# ESP32_S3_MINI.net
KiCad netlist of a schematic drawn in Altium Designer
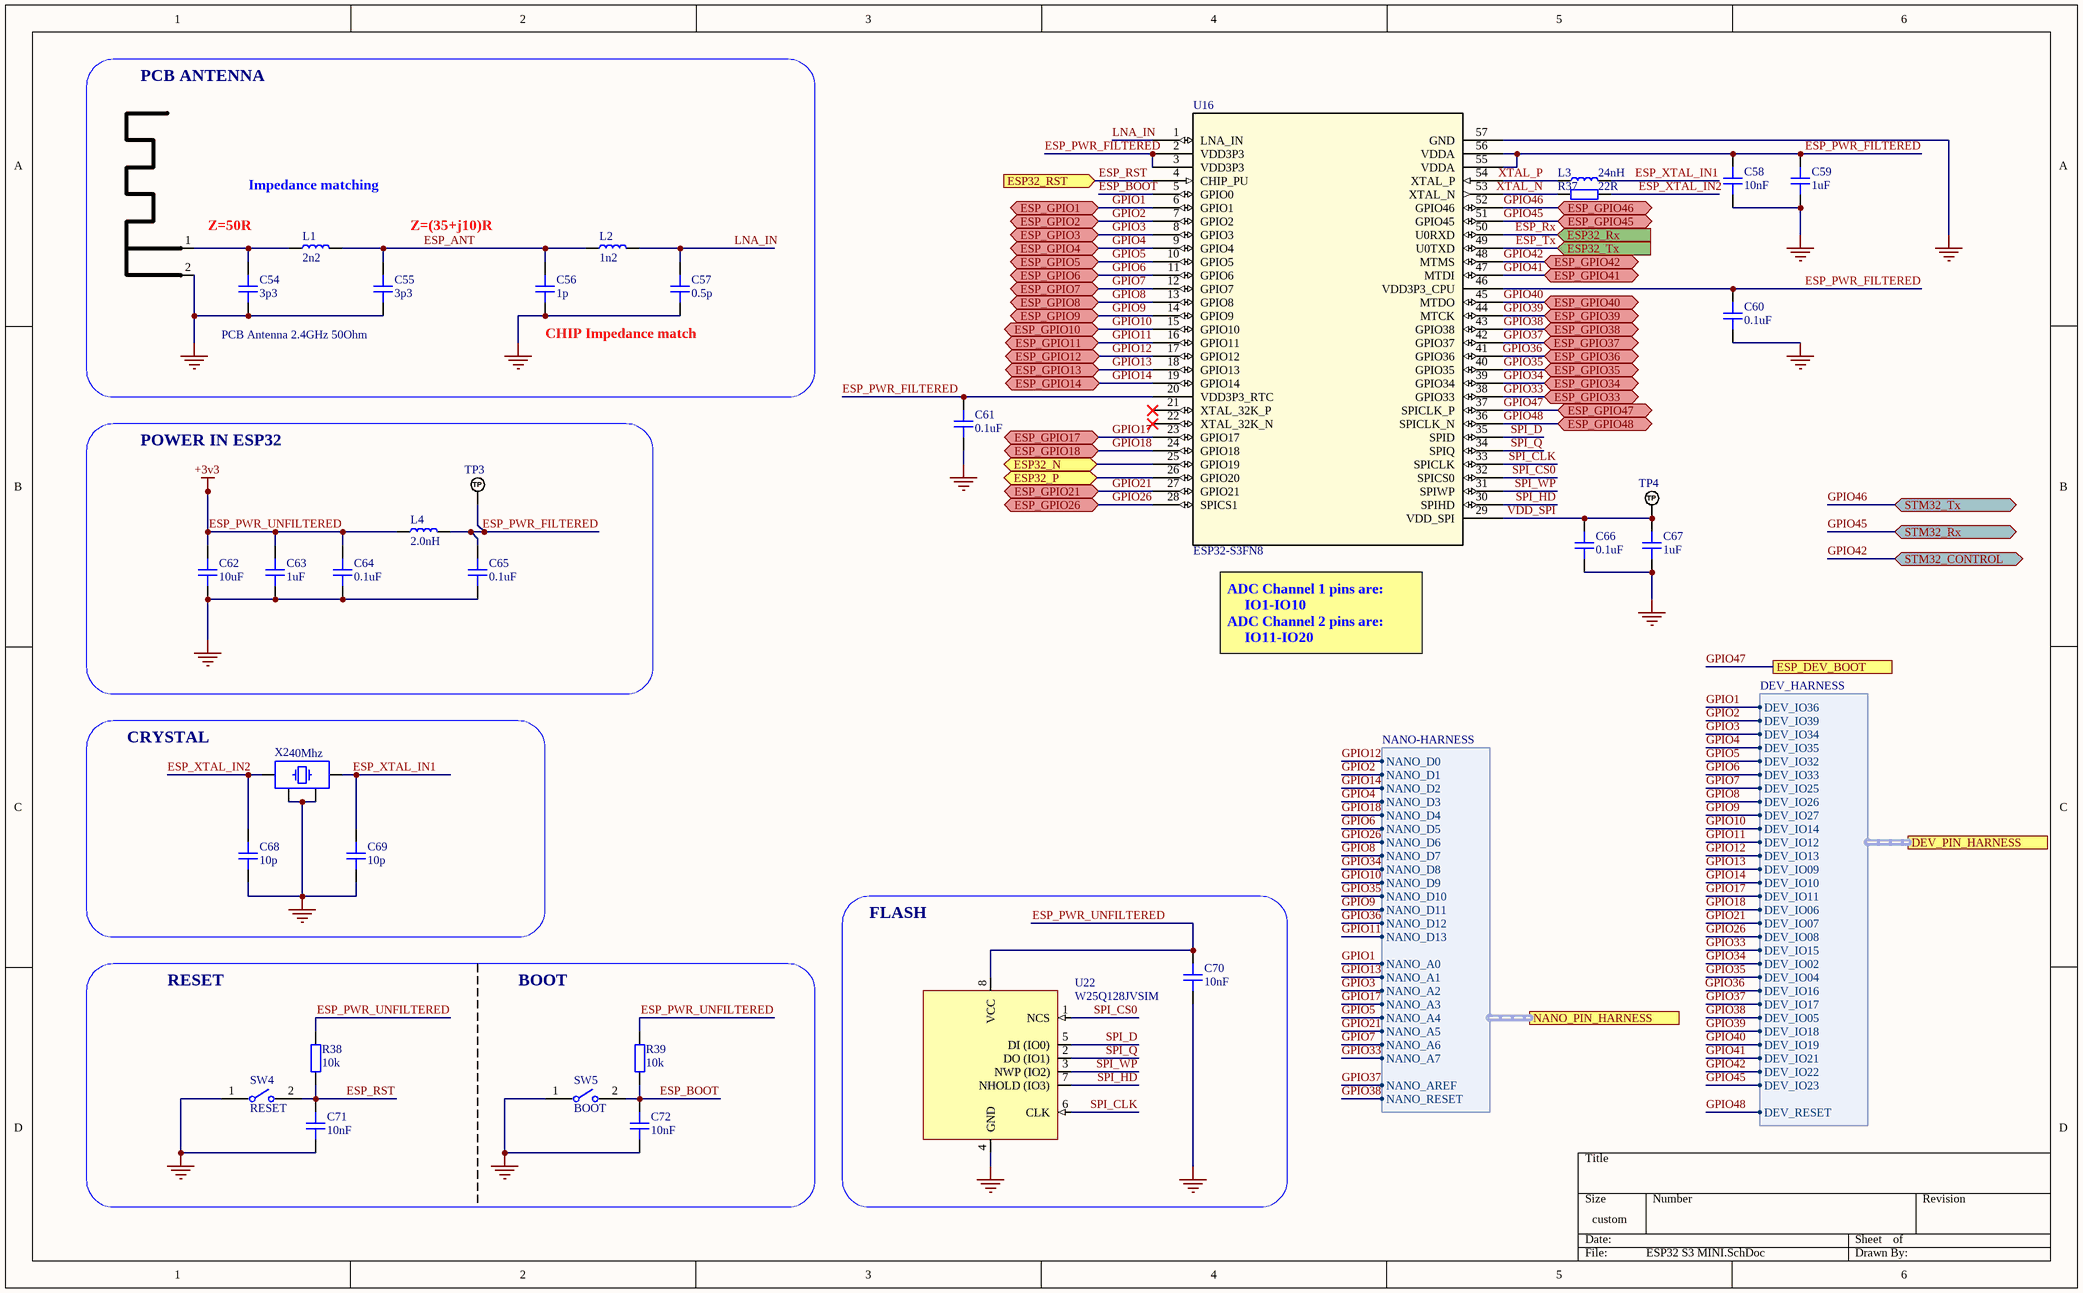
[diagram p0: ESP32 S3 MINI.SchDoc]

(export (version "E")
  (design (tool "Eeschema 10.0.6"))
  (components
    (comp (ref "ANT1")
      (value "PCB Antenna 2.4GHz 50Ohm")
      (footprint "ANT_IFA_USB_2_4GHZ_50R")
      (description "Inverted F 2.4GHz ISM PCB Antenna 50 Ohm")
      (libsource (lib "Schematic-Lib-PhilsLab") (part "ANT_IFA_USB_2_4GHZ_50R"))
    )
    (comp (ref "C54")
      (value "3p3")
      (footprint "CAP_0603")
      (description "Capacitor SMD 0603")
      (libsource (lib "Schematic-Lib-PhilsLab") (part "CAP_0603"))
    )
    (comp (ref "C55")
      (value "3p3")
      (footprint "CAP_0603")
      (description "Capacitor SMD 0603")
      (libsource (lib "Schematic-Lib-PhilsLab") (part "CAP_0603"))
    )
    (comp (ref "C56")
      (value "1p")
      (footprint "CAP_0603")
      (description "Capacitor SMD 0603")
      (libsource (lib "Schematic-Lib-PhilsLab") (part "CAP_0603"))
    )
    (comp (ref "C57")
      (value "0.5p")
      (footprint "CAP_0603")
      (description "Capacitor SMD 0603")
      (libsource (lib "Schematic-Lib-PhilsLab") (part "CAP_0603"))
    )
    (comp (ref "C58")
      (value "10nF")
      (footprint "CAP_0603")
      (description "Capacitor SMD 0603")
      (libsource (lib "Schematic-Lib-PhilsLab") (part "CAP_0603"))
    )
    (comp (ref "C59")
      (value "1uF")
      (footprint "CAP_0603")
      (description "Capacitor SMD 0603")
      (libsource (lib "Schematic-Lib-PhilsLab") (part "CAP_0603"))
    )
    (comp (ref "C60")
      (value "0.1uF")
      (footprint "CAP_0603")
      (description "Capacitor SMD 0603")
      (libsource (lib "Schematic-Lib-PhilsLab") (part "CAP_0603"))
    )
    (comp (ref "C61")
      (value "0.1uF")
      (footprint "CAP_0603")
      (description "Capacitor SMD 0603")
      (libsource (lib "Schematic-Lib-PhilsLab") (part "CAP_0603"))
    )
    (comp (ref "C62")
      (value "10uF")
      (footprint "CAP_0603")
      (description "Capacitor SMD 0603")
      (libsource (lib "Schematic-Lib-PhilsLab") (part "CAP_0603"))
    )
    (comp (ref "C63")
      (value "1uF")
      (footprint "CAP_0603")
      (description "Capacitor SMD 0603")
      (libsource (lib "Schematic-Lib-PhilsLab") (part "CAP_0603"))
    )
    (comp (ref "C64")
      (value "0.1uF")
      (footprint "CAP_0603")
      (description "Capacitor SMD 0603")
      (libsource (lib "Schematic-Lib-PhilsLab") (part "CAP_0603"))
    )
    (comp (ref "C65")
      (value "0.1uF")
      (footprint "CAP_0603")
      (description "Capacitor SMD 0603")
      (libsource (lib "Schematic-Lib-PhilsLab") (part "CAP_0603"))
    )
    (comp (ref "C66")
      (value "0.1uF")
      (footprint "CAP_0603")
      (description "Capacitor SMD 0603")
      (libsource (lib "Schematic-Lib-PhilsLab") (part "CAP_0603"))
    )
    (comp (ref "C67")
      (value "1uF")
      (footprint "CAP_0603")
      (description "Capacitor SMD 0603")
      (libsource (lib "Schematic-Lib-PhilsLab") (part "CAP_0603"))
    )
    (comp (ref "C68")
      (value "10p")
      (footprint "CAP_0603")
      (description "Capacitor SMD 0603")
      (libsource (lib "Schematic-Lib-PhilsLab") (part "CAP_0603"))
    )
    (comp (ref "C69")
      (value "10p")
      (footprint "CAP_0603")
      (description "Capacitor SMD 0603")
      (libsource (lib "Schematic-Lib-PhilsLab") (part "CAP_0603"))
    )
    (comp (ref "C70")
      (value "10nF")
      (footprint "CAP_0603")
      (description "Capacitor SMD 0603")
      (libsource (lib "Schematic-Lib-PhilsLab") (part "CAP_0603"))
    )
    (comp (ref "C71")
      (value "10nF")
      (footprint "CAP_0603")
      (description "Capacitor SMD 0603")
      (libsource (lib "Schematic-Lib-PhilsLab") (part "CAP_0603"))
    )
    (comp (ref "C72")
      (value "10nF")
      (footprint "CAP_0603")
      (description "Capacitor SMD 0603")
      (libsource (lib "Schematic-Lib-PhilsLab") (part "CAP_0603"))
    )
    (comp (ref "L1")
      (value "2n2")
      (footprint "IND_0603")
      (description "Inductor SMD 0603")
      (libsource (lib "Schematic-Lib-PhilsLab") (part "IND_0603"))
    )
    (comp (ref "L2")
      (value "1n2")
      (footprint "IND_0603")
      (description "Inductor SMD 0603")
      (libsource (lib "Schematic-Lib-PhilsLab") (part "IND_0603"))
    )
    (comp (ref "L3")
      (value "24nH")
      (footprint "IND_0603")
      (description "Inductor SMD 0603")
      (libsource (lib "Schematic-Lib-PhilsLab") (part "IND_0603"))
    )
    (comp (ref "L4")
      (value "2.0nH")
      (footprint "IND_0603")
      (description "Inductor SMD 0603")
      (libsource (lib "Schematic-Lib-PhilsLab") (part "IND_0603"))
    )
    (comp (ref "R37")
      (value "22R")
      (footprint "RES_0603")
      (description "Resistor SMD 0603")
      (libsource (lib "Schematic-Lib-PhilsLab") (part "RES_0603"))
    )
    (comp (ref "R38")
      (value "10k")
      (footprint "RES_0603")
      (description "Resistor SMD 0603")
      (libsource (lib "Schematic-Lib-PhilsLab") (part "RES_0603"))
    )
    (comp (ref "R39")
      (value "10k")
      (footprint "RES_0603")
      (description "Resistor SMD 0603")
      (libsource (lib "Schematic-Lib-PhilsLab") (part "RES_0603"))
    )
    (comp (ref "SW4")
      (value "RESET")
      (footprint "FP-B3U-1000P-MFG")
      (description "SWITCH TACTILE SPST-NO 0.05A 12V")
      (libsource (lib "Altium Content Vault") (part "ae622034201233ca1abcedc05908f33"))
    )
    (comp (ref "SW5")
      (value "BOOT")
      (footprint "FP-B3U-1000P-MFG")
      (description "SWITCH TACTILE SPST-NO 0.05A 12V")
      (libsource (lib "Altium Content Vault") (part "ae622034201233ca1abcedc05908f33"))
    )
    (comp (ref "TP3")
      (value "TP_NOBOM")
      (footprint "PAD_RND_1MM")
      (description "Test Point Round 1mm (NO BOM)")
      (libsource (lib "Schematic-Lib-PhilsLab") (part "TEST_POINT_RND_1MM"))
    )
    (comp (ref "TP4")
      (value "TP_NOBOM")
      (footprint "PAD_RND_1MM")
      (description "Test Point Round 1mm (NO BOM)")
      (libsource (lib "Schematic-Lib-PhilsLab") (part "TEST_POINT_RND_1MM"))
    )
    (comp (ref "U16")
      (value "ESP32-S3FN8")
      (footprint "ESP32-S3FN8:QFN56_7X7_EXP")
      (description "No Description Available")
      (fields (field (name "COPYRIGHT") "Copyright (C) 2025 Ultra Librarian. All rights reserved."))
      (libsource (lib "ESP32-S3FN8") (part "ESP32-S3FN8"))
    )
    (comp (ref "U22")
      (value "W25Q128JVSIM")
      (footprint "SOIC-8")
      (description "128M-BIT\r\nSERIAL FLASH MEMORY WITH\r\nDUAL/QUAD SPI & QPI & DTR SOIC-8")
      (fields (field (name "MANUFACTURER") "Winbond"))
      (libsource (lib "Schematic-Lib-PhilsLab") (part "W25Q128JVSIM"))
    )
    (comp (ref "X2")
      (value "40Mhz")
      (footprint "XTAL_3225")
      (description "Crystal SMD 24MHz 10PPM 7pF 3225")
      (fields
        (field (name "MANUFACTURER") "Epson")
        (field (name "MANUFACTURER PART NUMBER") "TSX-3225 24.0000MF15X-AC")
      )
      (libsource (lib "Schematic-Lib-PhilsLab") (part "TSX-3225_24.0000MF15X-AC"))
    )
  )
  (nets
    (net (code "3") (name "+3v3") (class "Default")
      (node (ref "C62") (pin "2") (pinfunction "2_2") (pintype "passive"))
      (node (ref "C63") (pin "2") (pinfunction "2_2") (pintype "passive"))
      (node (ref "C64") (pin "2") (pinfunction "2_2") (pintype "passive"))
      (node (ref "C70") (pin "2") (pinfunction "2_2") (pintype "passive"))
      (node (ref "L4") (pin "1") (pinfunction "1_1") (pintype "passive"))
      (node (ref "R38") (pin "2") (pinfunction "2_2") (pintype "passive"))
      (node (ref "R39") (pin "2") (pinfunction "2_2") (pintype "passive"))
      (node (ref "U22") (pin "8") (pinfunction "VCC_8") (pintype "power_in"))
    )
    (net (code "4") (name "/ESP32_N") (class "Default")
      (node (ref "U16") (pin "25") (pinfunction "GPIO19_25") (pintype "bidirectional"))
    )
    (net (code "5") (name "/ESP32_P") (class "Default")
      (node (ref "U16") (pin "26") (pinfunction "GPIO20_26") (pintype "bidirectional"))
    )
    (net (code "6") (name "/ESP_ANT") (class "Default")
      (node (ref "C55") (pin "2") (pinfunction "2_2") (pintype "passive"))
      (node (ref "C56") (pin "2") (pinfunction "2_2") (pintype "passive"))
      (node (ref "L1") (pin "2") (pinfunction "2_2") (pintype "passive"))
      (node (ref "L2") (pin "1") (pinfunction "1_1") (pintype "passive"))
    )
    (net (code "7") (name "/ESP_BOOT") (class "Default")
      (node (ref "C72") (pin "2") (pinfunction "2_2") (pintype "passive"))
      (node (ref "R39") (pin "1") (pinfunction "1_1") (pintype "passive"))
      (node (ref "SW5") (pin "2") (pinfunction "2_2") (pintype "passive"))
      (node (ref "U16") (pin "5") (pinfunction "GPIO0_5") (pintype "bidirectional"))
    )
    (net (code "8") (name "/ESP_PWR_FILTERED") (class "Default")
      (node (ref "C58") (pin "2") (pinfunction "2_2") (pintype "passive"))
      (node (ref "C59") (pin "2") (pinfunction "2_2") (pintype "passive"))
      (node (ref "C60") (pin "2") (pinfunction "2_2") (pintype "passive"))
      (node (ref "C61") (pin "2") (pinfunction "2_2") (pintype "passive"))
      (node (ref "C65") (pin "2") (pinfunction "2_2") (pintype "passive"))
      (node (ref "L4") (pin "2") (pinfunction "2_2") (pintype "passive"))
      (node (ref "TP3") (pin "1") (pinfunction "TP_1") (pintype "passive"))
      (node (ref "U16") (pin "2") (pinfunction "VDD3P3_2") (pintype "power_in"))
      (node (ref "U16") (pin "20") (pinfunction "VDD3P3_RTC_20") (pintype "power_in"))
      (node (ref "U16") (pin "3") (pinfunction "VDD3P3_3") (pintype "power_in"))
      (node (ref "U16") (pin "46") (pinfunction "VDD3P3_CPU_46") (pintype "power_in"))
      (node (ref "U16") (pin "55") (pinfunction "VDDA_55") (pintype "power_in"))
      (node (ref "U16") (pin "56") (pinfunction "VDDA_56") (pintype "power_in"))
    )
    (net (code "9") (name "/ESP_RST") (class "Default")
      (node (ref "C71") (pin "2") (pinfunction "2_2") (pintype "passive"))
      (node (ref "R38") (pin "1") (pinfunction "1_1") (pintype "passive"))
      (node (ref "SW4") (pin "2") (pinfunction "2_2") (pintype "passive"))
      (node (ref "U16") (pin "4") (pinfunction "CHIP_PU_4") (pintype "input"))
    )
    (net (code "10") (name "/ESP_Rx") (class "Default")
      (node (ref "U16") (pin "50") (pinfunction "U0RXD_50") (pintype "bidirectional"))
    )
    (net (code "11") (name "/ESP_Tx") (class "Default")
      (node (ref "U16") (pin "49") (pinfunction "U0TXD_49") (pintype "bidirectional"))
    )
    (net (code "12") (name "/ESP_XTAL_IN1") (class "Default")
      (node (ref "C69") (pin "2") (pinfunction "2_2") (pintype "passive"))
      (node (ref "L3") (pin "2") (pinfunction "2_2") (pintype "passive"))
      (node (ref "X2") (pin "3") (pinfunction "3_3") (pintype "passive"))
    )
    (net (code "13") (name "/ESP_XTAL_IN2") (class "Default")
      (node (ref "C68") (pin "2") (pinfunction "2_2") (pintype "passive"))
      (node (ref "R37") (pin "1") (pinfunction "1_1") (pintype "passive"))
      (node (ref "X2") (pin "1") (pinfunction "1_1") (pintype "passive"))
    )
    (net (code "14") (name "/GPIO1") (class "Default")
      (node (ref "U16") (pin "6") (pinfunction "GPIO1_6") (pintype "bidirectional"))
    )
    (net (code "15") (name "/GPIO2") (class "Default")
      (node (ref "U16") (pin "7") (pinfunction "GPIO2_7") (pintype "bidirectional"))
    )
    (net (code "16") (name "/GPIO3") (class "Default")
      (node (ref "U16") (pin "8") (pinfunction "GPIO3_8") (pintype "bidirectional"))
    )
    (net (code "17") (name "/GPIO4") (class "Default")
      (node (ref "U16") (pin "9") (pinfunction "GPIO4_9") (pintype "bidirectional"))
    )
    (net (code "18") (name "/GPIO5") (class "Default")
      (node (ref "U16") (pin "10") (pinfunction "GPIO5_10") (pintype "bidirectional"))
    )
    (net (code "19") (name "/GPIO6") (class "Default")
      (node (ref "U16") (pin "11") (pinfunction "GPIO6_11") (pintype "bidirectional"))
    )
    (net (code "20") (name "/GPIO7") (class "Default")
      (node (ref "U16") (pin "12") (pinfunction "GPIO7_12") (pintype "bidirectional"))
    )
    (net (code "21") (name "/GPIO8") (class "Default")
      (node (ref "U16") (pin "13") (pinfunction "GPIO8_13") (pintype "bidirectional"))
    )
    (net (code "22") (name "/GPIO9") (class "Default")
      (node (ref "U16") (pin "14") (pinfunction "GPIO9_14") (pintype "bidirectional"))
    )
    (net (code "23") (name "/GPIO10") (class "Default")
      (node (ref "U16") (pin "15") (pinfunction "GPIO10_15") (pintype "bidirectional"))
    )
    (net (code "24") (name "/GPIO11") (class "Default")
      (node (ref "U16") (pin "16") (pinfunction "GPIO11_16") (pintype "bidirectional"))
    )
    (net (code "25") (name "/GPIO12") (class "Default")
      (node (ref "U16") (pin "17") (pinfunction "GPIO12_17") (pintype "bidirectional"))
    )
    (net (code "26") (name "/GPIO13") (class "Default")
      (node (ref "U16") (pin "18") (pinfunction "GPIO13_18") (pintype "bidirectional"))
    )
    (net (code "27") (name "/GPIO14") (class "Default")
      (node (ref "U16") (pin "19") (pinfunction "GPIO14_19") (pintype "bidirectional"))
    )
    (net (code "28") (name "/GPIO17") (class "Default")
      (node (ref "U16") (pin "23") (pinfunction "GPIO17_23") (pintype "bidirectional"))
    )
    (net (code "29") (name "/GPIO18") (class "Default")
      (node (ref "U16") (pin "24") (pinfunction "GPIO18_24") (pintype "bidirectional"))
    )
    (net (code "30") (name "/GPIO21") (class "Default")
      (node (ref "U16") (pin "27") (pinfunction "GPIO21_27") (pintype "bidirectional"))
    )
    (net (code "31") (name "/GPIO26") (class "Default")
      (node (ref "U16") (pin "28") (pinfunction "SPICS1_28") (pintype "bidirectional"))
    )
    (net (code "32") (name "/GPIO33") (class "Default")
      (node (ref "U16") (pin "38") (pinfunction "GPIO33_38") (pintype "bidirectional"))
    )
    (net (code "33") (name "/GPIO34") (class "Default")
      (node (ref "U16") (pin "39") (pinfunction "GPIO34_39") (pintype "bidirectional"))
    )
    (net (code "34") (name "/GPIO35") (class "Default")
      (node (ref "U16") (pin "40") (pinfunction "GPIO35_40") (pintype "bidirectional"))
    )
    (net (code "35") (name "/GPIO36") (class "Default")
      (node (ref "U16") (pin "41") (pinfunction "GPIO36_41") (pintype "bidirectional"))
    )
    (net (code "36") (name "/GPIO37") (class "Default")
      (node (ref "U16") (pin "42") (pinfunction "GPIO37_42") (pintype "bidirectional"))
    )
    (net (code "37") (name "/GPIO38") (class "Default")
      (node (ref "U16") (pin "43") (pinfunction "GPIO38_43") (pintype "bidirectional"))
    )
    (net (code "38") (name "/GPIO39") (class "Default")
      (node (ref "U16") (pin "44") (pinfunction "MTCK_44") (pintype "bidirectional"))
    )
    (net (code "39") (name "/GPIO40") (class "Default")
      (node (ref "U16") (pin "45") (pinfunction "MTDO_45") (pintype "bidirectional"))
    )
    (net (code "40") (name "/GPIO41") (class "Default")
      (node (ref "U16") (pin "47") (pinfunction "MTDI_47") (pintype "bidirectional"))
    )
    (net (code "41") (name "/GPIO42") (class "Default")
      (node (ref "U16") (pin "48") (pinfunction "MTMS_48") (pintype "bidirectional"))
    )
    (net (code "42") (name "/GPIO45") (class "Default")
      (node (ref "U16") (pin "51") (pinfunction "GPIO45_51") (pintype "bidirectional"))
    )
    (net (code "43") (name "/GPIO46") (class "Default")
      (node (ref "U16") (pin "52") (pinfunction "GPIO46_52") (pintype "bidirectional"))
    )
    (net (code "44") (name "/GPIO47") (class "Default")
      (node (ref "U16") (pin "37") (pinfunction "SPICLK_P_37") (pintype "bidirectional"))
    )
    (net (code "45") (name "/GPIO48") (class "Default")
      (node (ref "U16") (pin "36") (pinfunction "SPICLK_N_36") (pintype "bidirectional"))
    )
    (net (code "46") (name "/LNA_IN") (class "Default")
      (node (ref "C57") (pin "2") (pinfunction "2_2") (pintype "passive"))
      (node (ref "L2") (pin "2") (pinfunction "2_2") (pintype "passive"))
      (node (ref "U16") (pin "1") (pinfunction "LNA_IN_1") (pintype "bidirectional"))
    )
    (net (code "47") (name "/SPI_CLK") (class "Default")
      (node (ref "U16") (pin "33") (pinfunction "SPICLK_33") (pintype "bidirectional"))
      (node (ref "U22") (pin "6") (pinfunction "CLK_6") (pintype "input"))
    )
    (net (code "48") (name "/SPI_CS0") (class "Default")
      (node (ref "U16") (pin "32") (pinfunction "SPICS0_32") (pintype "bidirectional"))
      (node (ref "U22") (pin "1") (pinfunction "NCS_1") (pintype "input"))
    )
    (net (code "49") (name "/SPI_D") (class "Default")
      (node (ref "U16") (pin "35") (pinfunction "SPID_35") (pintype "bidirectional"))
      (node (ref "U22") (pin "5") (pinfunction "DI_(IO0)_5") (pintype "bidirectional"))
    )
    (net (code "50") (name "/SPI_HD") (class "Default")
      (node (ref "U16") (pin "30") (pinfunction "SPIHD_30") (pintype "bidirectional"))
      (node (ref "U22") (pin "7") (pinfunction "NHOLD_(IO3)_7") (pintype "bidirectional"))
    )
    (net (code "51") (name "/SPI_Q") (class "Default")
      (node (ref "U16") (pin "34") (pinfunction "SPIQ_34") (pintype "bidirectional"))
      (node (ref "U22") (pin "2") (pinfunction "DO_(IO1)_2") (pintype "bidirectional"))
    )
    (net (code "52") (name "/SPI_WP") (class "Default")
      (node (ref "U16") (pin "31") (pinfunction "SPIWP_31") (pintype "bidirectional"))
      (node (ref "U22") (pin "3") (pinfunction "NWP_(IO2)_3") (pintype "bidirectional"))
    )
    (net (code "53") (name "/VDD_SPI") (class "Default")
      (node (ref "C66") (pin "2") (pinfunction "2_2") (pintype "passive"))
      (node (ref "C67") (pin "2") (pinfunction "2_2") (pintype "passive"))
      (node (ref "TP4") (pin "1") (pinfunction "TP_1") (pintype "passive"))
      (node (ref "U16") (pin "29") (pinfunction "VDD_SPI_29") (pintype "power_in"))
    )
    (net (code "54") (name "/XTAL_N") (class "Default")
      (node (ref "R37") (pin "2") (pinfunction "2_2") (pintype "passive"))
      (node (ref "U16") (pin "53") (pinfunction "XTAL_N_53") (pintype "output"))
    )
    (net (code "55") (name "/XTAL_P") (class "Default")
      (node (ref "L3") (pin "1") (pinfunction "1_1") (pintype "passive"))
      (node (ref "U16") (pin "54") (pinfunction "XTAL_P_54") (pintype "input"))
    )
    (net (code "58") (name "GND") (class "Default")
      (node (ref "ANT1") (pin "2") (pinfunction "GND_2") (pintype "passive"))
      (node (ref "C54") (pin "1") (pinfunction "1_1") (pintype "passive"))
      (node (ref "C55") (pin "1") (pinfunction "1_1") (pintype "passive"))
      (node (ref "C56") (pin "1") (pinfunction "1_1") (pintype "passive"))
      (node (ref "C57") (pin "1") (pinfunction "1_1") (pintype "passive"))
      (node (ref "C58") (pin "1") (pinfunction "1_1") (pintype "passive"))
      (node (ref "C59") (pin "1") (pinfunction "1_1") (pintype "passive"))
      (node (ref "C60") (pin "1") (pinfunction "1_1") (pintype "passive"))
      (node (ref "C61") (pin "1") (pinfunction "1_1") (pintype "passive"))
      (node (ref "C62") (pin "1") (pinfunction "1_1") (pintype "passive"))
      (node (ref "C63") (pin "1") (pinfunction "1_1") (pintype "passive"))
      (node (ref "C64") (pin "1") (pinfunction "1_1") (pintype "passive"))
      (node (ref "C65") (pin "1") (pinfunction "1_1") (pintype "passive"))
      (node (ref "C66") (pin "1") (pinfunction "1_1") (pintype "passive"))
      (node (ref "C67") (pin "1") (pinfunction "1_1") (pintype "passive"))
      (node (ref "C68") (pin "1") (pinfunction "1_1") (pintype "passive"))
      (node (ref "C69") (pin "1") (pinfunction "1_1") (pintype "passive"))
      (node (ref "C70") (pin "1") (pinfunction "1_1") (pintype "passive"))
      (node (ref "C71") (pin "1") (pinfunction "1_1") (pintype "passive"))
      (node (ref "C72") (pin "1") (pinfunction "1_1") (pintype "passive"))
      (node (ref "SW4") (pin "1") (pinfunction "1_1") (pintype "passive"))
      (node (ref "SW5") (pin "1") (pinfunction "1_1") (pintype "passive"))
      (node (ref "U16") (pin "57") (pinfunction "GND_57") (pintype "power_in"))
      (node (ref "U22") (pin "4") (pinfunction "GND_4") (pintype "power_in"))
      (node (ref "X2") (pin "2") (pinfunction "2_2") (pintype "passive"))
      (node (ref "X2") (pin "4") (pinfunction "4_4") (pintype "passive"))
    )
    (net (code "59") (name "Net-(ANT1-RF)") (class "Default")
      (node (ref "ANT1") (pin "1") (pinfunction "RF_1") (pintype "passive"))
      (node (ref "C54") (pin "2") (pinfunction "2_2") (pintype "passive"))
      (node (ref "L1") (pin "1") (pinfunction "1_1") (pintype "passive"))
    )
    (net (code "60") (name "unconnected-(U16-XTAL_32K_N-Pad22)") (class "Default")
      (node (ref "U16") (pin "22") (pinfunction "XTAL_32K_N_22") (pintype "bidirectional+no_connect"))
    )
    (net (code "61") (name "unconnected-(U16-XTAL_32K_P-Pad21)") (class "Default")
      (node (ref "U16") (pin "21") (pinfunction "XTAL_32K_P_21") (pintype "bidirectional+no_connect"))
    )
  )
)
